# RS485.net
KiCad netlist of a schematic drawn in Altium Designer
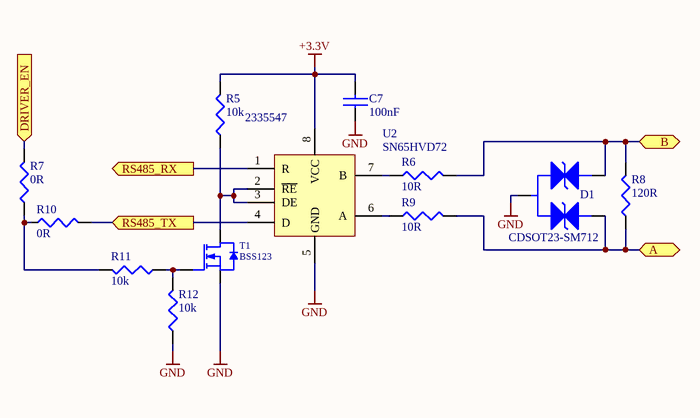
[diagram p0: RS485.SchDoc]

(export (version "E")
  (design (tool "Eeschema 10.0.6"))
  (components
    (comp (ref "C7")
      (value "100nF")
      (footprint "CAP0603")
      (description "MURATA - GRM188R71C104KA01J - CAP, MLCC, X7R, 0.1UF, 16V, 0603")
      (fields
        (field (name "MANUFACTURER") "MURATA")
        (field (name "MANUFACTURER PART NUMBER") "GRM188R71C104KA01J")
      )
      (libsource (lib "Passive") (part "C - 100nF"))
    )
    (comp (ref "D1")
      (value "CDSOT23-SM712")
      (footprint "SOT23-3AL")
      (description "TVS Diode, CDSOT23 Series, Bidirectional, 12 V, 26 V, SOT-23, 3 Pins")
      (fields
        (field (name "MANUFACTURER") "DIODES INC.")
        (field (name "MANUFACTURER PART NUMBER") "1N4148W-7-F.")
      )
      (libsource (lib "Active") (part "D_TVS - CDSOT23-SM712"))
    )
    (comp (ref "R5")
      (value "10k")
      (footprint "RES0603")
      (description "MULTICOMP - MCMR06X103 JTL - RES, CERAMIC, 10K, 5%, 0.1W, 0603")
      (fields
        (field (name "MANUFACTURER") "MULTICOMP")
        (field (name "MANUFACTURER PART NUMBER") "MCMR06X103 JTL")
      )
      (libsource (lib "Passive") (part "R - 10k"))
    )
    (comp (ref "R6")
      (value "10R")
      (footprint "RES0603")
      (description "VISHAY - RCA060310R0FKEA - RES, AUTO, THICK FILM, 10R, 1%, 0603")
      (fields
        (field (name "MANUFACTURER") "VISHAY")
        (field (name "MANUFACTURER PART NUMBER") "RCA060310R0FKEA")
      )
      (libsource (lib "Passive") (part "R - 10R"))
    )
    (comp (ref "R7")
      (value "0R")
      (footprint "RES0603")
      (description "BOURNS - CR0603-J/-000ELF - RES, THICK FILM, 0R, 5%, 0.1W, 0603")
      (fields
        (field (name "MANUFACTURER") "BOURNS")
        (field (name "MANUFACTURER PART NUMBER") "CR0603-J/-000ELF")
      )
      (libsource (lib "Passive") (part "R - 0R"))
    )
    (comp (ref "R8")
      (value "120R")
      (footprint "RES0603")
      (description "RES SMD 120 OHM 1% 1/4W 0603")
      (fields
        (field (name "MANUFACTURER") "Vishay")
        (field (name "MANUFACTURER PART NUMBER") "CRCW0603120RFKEAHP")
      )
      (libsource (lib "Passive") (part "R - 120R"))
    )
    (comp (ref "R9")
      (value "10R")
      (footprint "RES0603")
      (description "VISHAY - RCA060310R0FKEA - RES, AUTO, THICK FILM, 10R, 1%, 0603")
      (fields
        (field (name "MANUFACTURER") "VISHAY")
        (field (name "MANUFACTURER PART NUMBER") "RCA060310R0FKEA")
      )
      (libsource (lib "Passive") (part "R - 10R"))
    )
    (comp (ref "R10")
      (value "0R")
      (footprint "RES0603")
      (description "BOURNS - CR0603-J/-000ELF - RES, THICK FILM, 0R, 5%, 0.1W, 0603")
      (fields
        (field (name "MANUFACTURER") "BOURNS")
        (field (name "MANUFACTURER PART NUMBER") "CR0603-J/-000ELF")
      )
      (libsource (lib "Passive") (part "R - 0R"))
    )
    (comp (ref "R11")
      (value "10k")
      (footprint "RES0603")
      (description "MULTICOMP - MCMR06X103 JTL - RES, CERAMIC, 10K, 5%, 0.1W, 0603")
      (fields
        (field (name "MANUFACTURER") "MULTICOMP")
        (field (name "MANUFACTURER PART NUMBER") "MCMR06X103 JTL")
      )
      (libsource (lib "Passive") (part "R - 10k"))
    )
    (comp (ref "R12")
      (value "10k")
      (footprint "RES0603")
      (description "MULTICOMP - MCMR06X103 JTL - RES, CERAMIC, 10K, 5%, 0.1W, 0603")
      (fields
        (field (name "MANUFACTURER") "MULTICOMP")
        (field (name "MANUFACTURER PART NUMBER") "MCMR06X103 JTL")
      )
      (libsource (lib "Passive") (part "R - 10k"))
    )
    (comp (ref "T1")
      (value "BSS123")
      (footprint "Active:SOT23-3AL")
      (description "N-Channel Vds = 100V, Id = 170 mA")
      (libsource (lib "Active") (part "T_M - BSS123"))
    )
    (comp (ref "U2")
      (value "SN65HVD72")
      (footprint "SOIC-8 REFLOW")
      (fields (field (name "SUPPLIER PART NUMBER 1") "2335547"))
      (libsource (lib "Active") (part "INT - SN65HVD72"))
    )
  )
  (nets
    (net (code "1") (name "+3.3V") (class "Default")
      (node (ref "C7") (pin "2") (pinfunction "2_2") (pintype "passive"))
      (node (ref "R5") (pin "2") (pinfunction "2_2") (pintype "passive"))
      (node (ref "U2") (pin "8") (pinfunction "VCC_8") (pintype "passive"))
    )
    (net (code "2") (name "/A") (class "Default")
      (node (ref "D1") (pin "2") (pinfunction "cathode_2") (pintype "passive"))
      (node (ref "R8") (pin "1") (pinfunction "1_1") (pintype "passive"))
      (node (ref "R9") (pin "2") (pinfunction "2_2") (pintype "passive"))
    )
    (net (code "3") (name "/B") (class "Default")
      (node (ref "D1") (pin "1") (pinfunction "cathode_1") (pintype "passive"))
      (node (ref "R6") (pin "2") (pinfunction "2_2") (pintype "passive"))
      (node (ref "R8") (pin "2") (pinfunction "2_2") (pintype "passive"))
    )
    (net (code "4") (name "/DRIVER_EN") (class "Default")
      (node (ref "R7") (pin "2") (pinfunction "2_2") (pintype "passive"))
    )
    (net (code "5") (name "/RS485_RX") (class "Default")
      (node (ref "U2") (pin "1") (pinfunction "R_1") (pintype "passive"))
    )
    (net (code "6") (name "/RS485_TX") (class "Default")
      (node (ref "R10") (pin "2") (pinfunction "2_2") (pintype "passive"))
      (node (ref "U2") (pin "4") (pinfunction "D_4") (pintype "passive"))
    )
    (net (code "7") (name "GND") (class "Default")
      (node (ref "C7") (pin "1") (pinfunction "1_1") (pintype "passive"))
      (node (ref "D1") (pin "3") (pinfunction "ANODE_3") (pintype "passive"))
      (node (ref "R12") (pin "1") (pinfunction "1_1") (pintype "passive"))
      (node (ref "T1") (pin "2") (pinfunction "S_2") (pintype "passive"))
      (node (ref "U2") (pin "5") (pinfunction "GND_5") (pintype "passive"))
    )
    (net (code "8") (name "Net-(R10-Pad1)") (class "Default")
      (node (ref "R10") (pin "1") (pinfunction "1_1") (pintype "passive"))
      (node (ref "R11") (pin "2") (pinfunction "2_2") (pintype "passive"))
      (node (ref "R7") (pin "1") (pinfunction "1_1") (pintype "passive"))
    )
    (net (code "9") (name "Net-(T1-D)") (class "Default")
      (node (ref "R5") (pin "1") (pinfunction "1_1") (pintype "passive"))
      (node (ref "T1") (pin "3") (pinfunction "D_3") (pintype "passive"))
      (node (ref "U2") (pin "2") (pinfunction "~{RE}_2") (pintype "passive"))
      (node (ref "U2") (pin "3") (pinfunction "DE_3") (pintype "passive"))
    )
    (net (code "10") (name "Net-(T1-G)") (class "Default")
      (node (ref "R11") (pin "1") (pinfunction "1_1") (pintype "passive"))
      (node (ref "R12") (pin "2") (pinfunction "2_2") (pintype "passive"))
      (node (ref "T1") (pin "1") (pinfunction "G_1") (pintype "passive"))
    )
    (net (code "11") (name "Net-(U2-A)") (class "Default")
      (node (ref "R9") (pin "1") (pinfunction "1_1") (pintype "passive"))
      (node (ref "U2") (pin "6") (pinfunction "A_6") (pintype "passive"))
    )
    (net (code "12") (name "Net-(U2-B)") (class "Default")
      (node (ref "R6") (pin "1") (pinfunction "1_1") (pintype "passive"))
      (node (ref "U2") (pin "7") (pinfunction "B_7") (pintype "passive"))
    )
  )
)
